# RGBParkLight16.net
KiCad netlist of a schematic drawn in Altium Designer
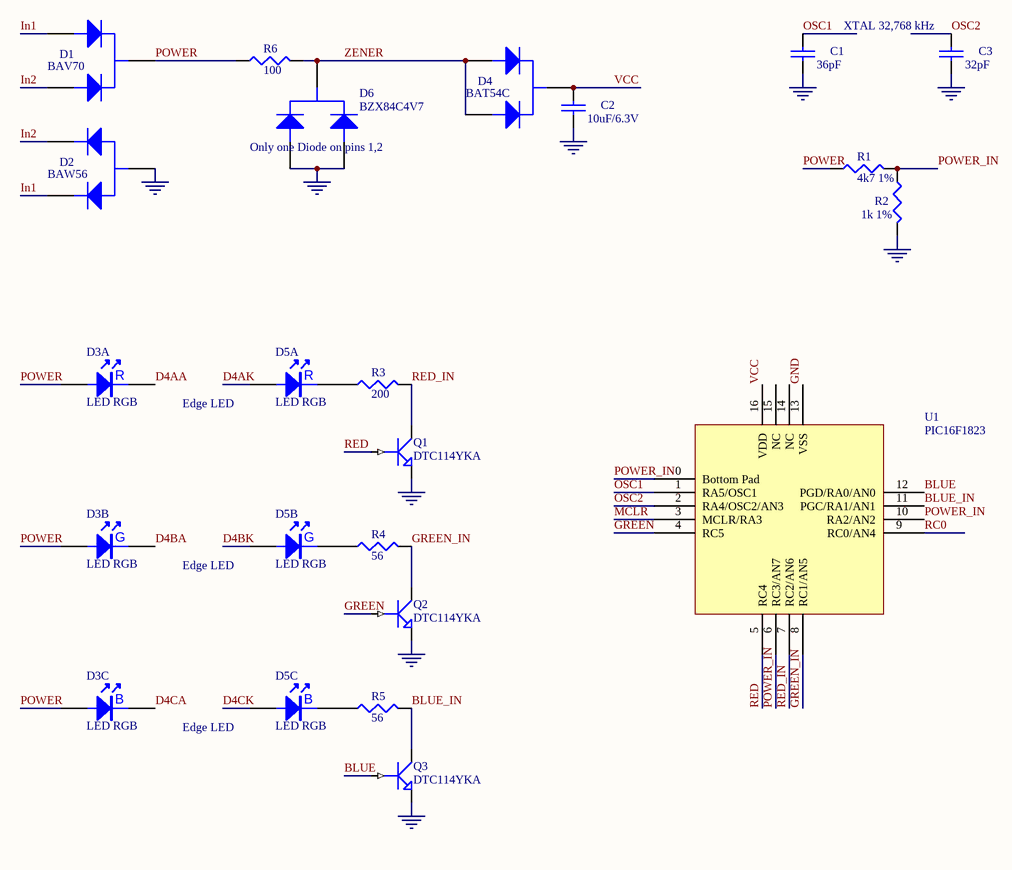
[diagram p0: RGBParkLight16.SCHDOC]

(export (version "E")
  (design (tool "Eeschema 10.0.6"))
  (components
    (comp (ref "C1")
      (value "36pF")
      (footprint "0603")
      (description "Capacitor")
      (libsource (lib "Miscellaneous Devices") (part "CAP"))
    )
    (comp (ref "C2")
      (value "10uF/6.3V")
      (footprint "0805")
      (description "Capacitor")
      (libsource (lib "Miscellaneous Devices") (part "CAP"))
    )
    (comp (ref "C3")
      (value "32pF")
      (footprint "0603")
      (description "Capacitor")
      (libsource (lib "Miscellaneous Devices") (part "CAP"))
    )
    (comp (ref "D1")
      (value "BAV70")
      (footprint "SOT-23")
      (libsource (lib "Devices") (part "DUAL DIODE BAV70"))
    )
    (comp (ref "D2")
      (value "BAW56")
      (footprint "SOT-23")
      (libsource (lib "Devices") (part "DUAL DIODE BAW56"))
    )
    (comp (ref "D3") (value "~") (footprint "AF-5060") (libsource (lib "Devices") (part "LED RGB")))
    (comp (ref "D4")
      (value "BAT54C")
      (footprint "SOT-23")
      (libsource (lib "Devices") (part "DUAL DIODE BAV70"))
    )
    (comp (ref "D5") (value "~") (footprint "AF-5060") (libsource (lib "Devices") (part "LED RGB")))
    (comp (ref "D6")
      (value "BZX84C4V7")
      (footprint "SOT-23")
      (libsource (lib "Devices") (part "DUAL DIODE BAV70"))
    )
    (comp (ref "Q1")
      (value "DTC114YKA")
      (footprint "SOT-23")
      (description "NPN Transistor")
      (libsource (lib "Miscellaneous Devices") (part "NPN1"))
    )
    (comp (ref "Q2")
      (value "DTC114YKA")
      (footprint "SOT-23")
      (description "NPN Transistor")
      (libsource (lib "Miscellaneous Devices") (part "NPN1"))
    )
    (comp (ref "Q3")
      (value "DTC114YKA")
      (footprint "SOT-23")
      (description "NPN Transistor")
      (libsource (lib "Miscellaneous Devices") (part "NPN1"))
    )
    (comp (ref "R1")
      (value "4k7 1%")
      (footprint "0603")
      (libsource (lib "Miscellaneous Devices") (part "RES1"))
    )
    (comp (ref "R2")
      (value "1k 1%")
      (footprint "0603")
      (libsource (lib "Miscellaneous Devices") (part "RES1"))
    )
    (comp (ref "R3") (value "200") (footprint "0805") (libsource (lib "Miscellaneous Devices") (part "RES1")))
    (comp (ref "R4") (value "56") (footprint "0805") (libsource (lib "Miscellaneous Devices") (part "RES1")))
    (comp (ref "R5") (value "56") (footprint "0805") (libsource (lib "Miscellaneous Devices") (part "RES1")))
    (comp (ref "R6") (value "100") (footprint "0603") (libsource (lib "Miscellaneous Devices") (part "RES1")))
    (comp (ref "U1")
      (value "PIC16F1823")
      (footprint "QFN16-ML")
      (description "Microchip Microcontroller with Central Pad")
      (libsource (lib "MCU") (part "PIC16F1823_0"))
    )
  )
  (nets
    (net (code "1") (name "/BLUE") (class "Default")
      (node (ref "Q3") (pin "1") (pinfunction "B_1") (pintype "input"))
      (node (ref "U1") (pin "12") (pinfunction "PGD/RA0/AN0_12") (pintype "passive"))
    )
    (net (code "2") (name "/BLUE_IN") (class "Default")
      (node (ref "Q3") (pin "2") (pinfunction "C_2") (pintype "passive"))
      (node (ref "R5") (pin "2") (pinfunction "2_2") (pintype "passive"))
      (node (ref "U1") (pin "11") (pinfunction "PGC/RA1/AN1_11") (pintype "passive"))
    )
    (net (code "3") (name "/D4AA") (class "Default")
      (node (ref "D3") (pin "4") (pinfunction "K_4") (pintype "passive"))
    )
    (net (code "4") (name "/D4AK") (class "Default")
      (node (ref "D5") (pin "3") (pinfunction "A_3") (pintype "passive"))
    )
    (net (code "5") (name "/D4BA") (class "Default")
      (node (ref "D3") (pin "5") (pinfunction "K_5") (pintype "passive"))
    )
    (net (code "6") (name "/D4BK") (class "Default")
      (node (ref "D5") (pin "2") (pinfunction "A_2") (pintype "passive"))
    )
    (net (code "7") (name "/D4CA") (class "Default")
      (node (ref "D3") (pin "6") (pinfunction "K_6") (pintype "passive"))
    )
    (net (code "8") (name "/D4CK") (class "Default")
      (node (ref "D5") (pin "1") (pinfunction "A_1") (pintype "passive"))
    )
    (net (code "9") (name "/GREEN") (class "Default")
      (node (ref "Q2") (pin "1") (pinfunction "B_1") (pintype "input"))
      (node (ref "U1") (pin "4") (pinfunction "RC5_4") (pintype "passive"))
    )
    (net (code "10") (name "/GREEN_IN") (class "Default")
      (node (ref "Q2") (pin "2") (pinfunction "C_2") (pintype "passive"))
      (node (ref "R4") (pin "2") (pinfunction "2_2") (pintype "passive"))
      (node (ref "U1") (pin "8") (pinfunction "RC1/AN5_8") (pintype "passive"))
    )
    (net (code "11") (name "/In1") (class "Default")
      (node (ref "D1") (pin "1") (pinfunction "A1_1") (pintype "passive"))
      (node (ref "D2") (pin "3") (pinfunction "K2_3") (pintype "passive"))
    )
    (net (code "12") (name "/In2") (class "Default")
      (node (ref "D1") (pin "3") (pinfunction "A2_3") (pintype "passive"))
      (node (ref "D2") (pin "1") (pinfunction "K1_1") (pintype "passive"))
    )
    (net (code "13") (name "/MCLR") (class "Default")
      (node (ref "U1") (pin "3") (pinfunction "MCLR/RA3_3") (pintype "passive"))
    )
    (net (code "14") (name "/OSC1") (class "Default")
      (node (ref "C1") (pin "1") (pinfunction "1_1") (pintype "passive"))
      (node (ref "U1") (pin "1") (pinfunction "RA5/OSC1_1") (pintype "passive"))
    )
    (net (code "15") (name "/OSC2") (class "Default")
      (node (ref "C3") (pin "1") (pinfunction "1_1") (pintype "passive"))
      (node (ref "U1") (pin "2") (pinfunction "RA4/OSC2/AN3_2") (pintype "passive"))
    )
    (net (code "16") (name "/POWER") (class "Default")
      (node (ref "D1") (pin "2") (pinfunction "K_2") (pintype "passive"))
      (node (ref "D3") (pin "1") (pinfunction "A_1") (pintype "passive"))
      (node (ref "D3") (pin "2") (pinfunction "A_2") (pintype "passive"))
      (node (ref "D3") (pin "3") (pinfunction "A_3") (pintype "passive"))
      (node (ref "R1") (pin "1") (pinfunction "1_1") (pintype "passive"))
      (node (ref "R6") (pin "1") (pinfunction "1_1") (pintype "passive"))
    )
    (net (code "17") (name "/POWER_IN") (class "Default")
      (node (ref "R1") (pin "2") (pinfunction "2_2") (pintype "passive"))
      (node (ref "R2") (pin "1") (pinfunction "1_1") (pintype "passive"))
      (node (ref "U1") (pin "0") (pinfunction "Bottom_Pad_0") (pintype "passive"))
      (node (ref "U1") (pin "10") (pinfunction "RA2/AN2_10") (pintype "passive"))
      (node (ref "U1") (pin "6") (pinfunction "RC3/AN7_6") (pintype "passive"))
    )
    (net (code "18") (name "/RC0") (class "Default")
      (node (ref "U1") (pin "9") (pinfunction "RC0/AN4_9") (pintype "passive"))
    )
    (net (code "19") (name "/RED") (class "Default")
      (node (ref "Q1") (pin "1") (pinfunction "B_1") (pintype "input"))
      (node (ref "U1") (pin "5") (pinfunction "RC4_5") (pintype "passive"))
    )
    (net (code "20") (name "/RED_IN") (class "Default")
      (node (ref "Q1") (pin "2") (pinfunction "C_2") (pintype "passive"))
      (node (ref "R3") (pin "2") (pinfunction "2_2") (pintype "passive"))
      (node (ref "U1") (pin "7") (pinfunction "RC2/AN6_7") (pintype "passive"))
    )
    (net (code "21") (name "/VCC") (class "Default")
      (node (ref "C2") (pin "1") (pinfunction "1_1") (pintype "passive"))
      (node (ref "D4") (pin "2") (pinfunction "K_2") (pintype "passive"))
      (node (ref "U1") (pin "16") (pinfunction "VDD_16") (pintype "passive"))
    )
    (net (code "22") (name "/ZENER") (class "Default")
      (node (ref "D4") (pin "1") (pinfunction "A1_1") (pintype "passive"))
      (node (ref "D4") (pin "3") (pinfunction "A2_3") (pintype "passive"))
      (node (ref "D6") (pin "2") (pinfunction "K_2") (pintype "passive"))
      (node (ref "R6") (pin "2") (pinfunction "2_2") (pintype "passive"))
    )
    (net (code "23") (name "GND") (class "Default")
      (node (ref "C1") (pin "2") (pinfunction "2_2") (pintype "passive"))
      (node (ref "C2") (pin "2") (pinfunction "2_2") (pintype "passive"))
      (node (ref "C3") (pin "2") (pinfunction "2_2") (pintype "passive"))
      (node (ref "D2") (pin "2") (pinfunction "A_2") (pintype "passive"))
      (node (ref "D6") (pin "1") (pinfunction "A1_1") (pintype "passive"))
      (node (ref "D6") (pin "3") (pinfunction "A2_3") (pintype "passive"))
      (node (ref "Q1") (pin "3") (pinfunction "E_3") (pintype "passive"))
      (node (ref "Q2") (pin "3") (pinfunction "E_3") (pintype "passive"))
      (node (ref "Q3") (pin "3") (pinfunction "E_3") (pintype "passive"))
      (node (ref "R2") (pin "2") (pinfunction "2_2") (pintype "passive"))
      (node (ref "U1") (pin "13") (pinfunction "VSS_13") (pintype "passive"))
    )
    (net (code "24") (name "Net-(D5A-K)") (class "Default")
      (node (ref "D5") (pin "4") (pinfunction "K_4") (pintype "passive"))
      (node (ref "R3") (pin "1") (pinfunction "1_1") (pintype "passive"))
    )
    (net (code "25") (name "Net-(D5B-K)") (class "Default")
      (node (ref "D5") (pin "5") (pinfunction "K_5") (pintype "passive"))
      (node (ref "R4") (pin "1") (pinfunction "1_1") (pintype "passive"))
    )
    (net (code "26") (name "Net-(D5C-K)") (class "Default")
      (node (ref "D5") (pin "6") (pinfunction "K_6") (pintype "passive"))
      (node (ref "R5") (pin "1") (pinfunction "1_1") (pintype "passive"))
    )
    (net (code "27") (name "unconnected-(U1-NC-Pad14)") (class "Default")
      (node (ref "U1") (pin "14") (pinfunction "NC_14") (pintype "passive"))
    )
    (net (code "28") (name "unconnected-(U1-NC-Pad15)") (class "Default")
      (node (ref "U1") (pin "15") (pinfunction "NC_15") (pintype "passive"))
    )
  )
)
